# Polarshield_v2_2a.net
KiCad netlist of a schematic drawn in EAGLE
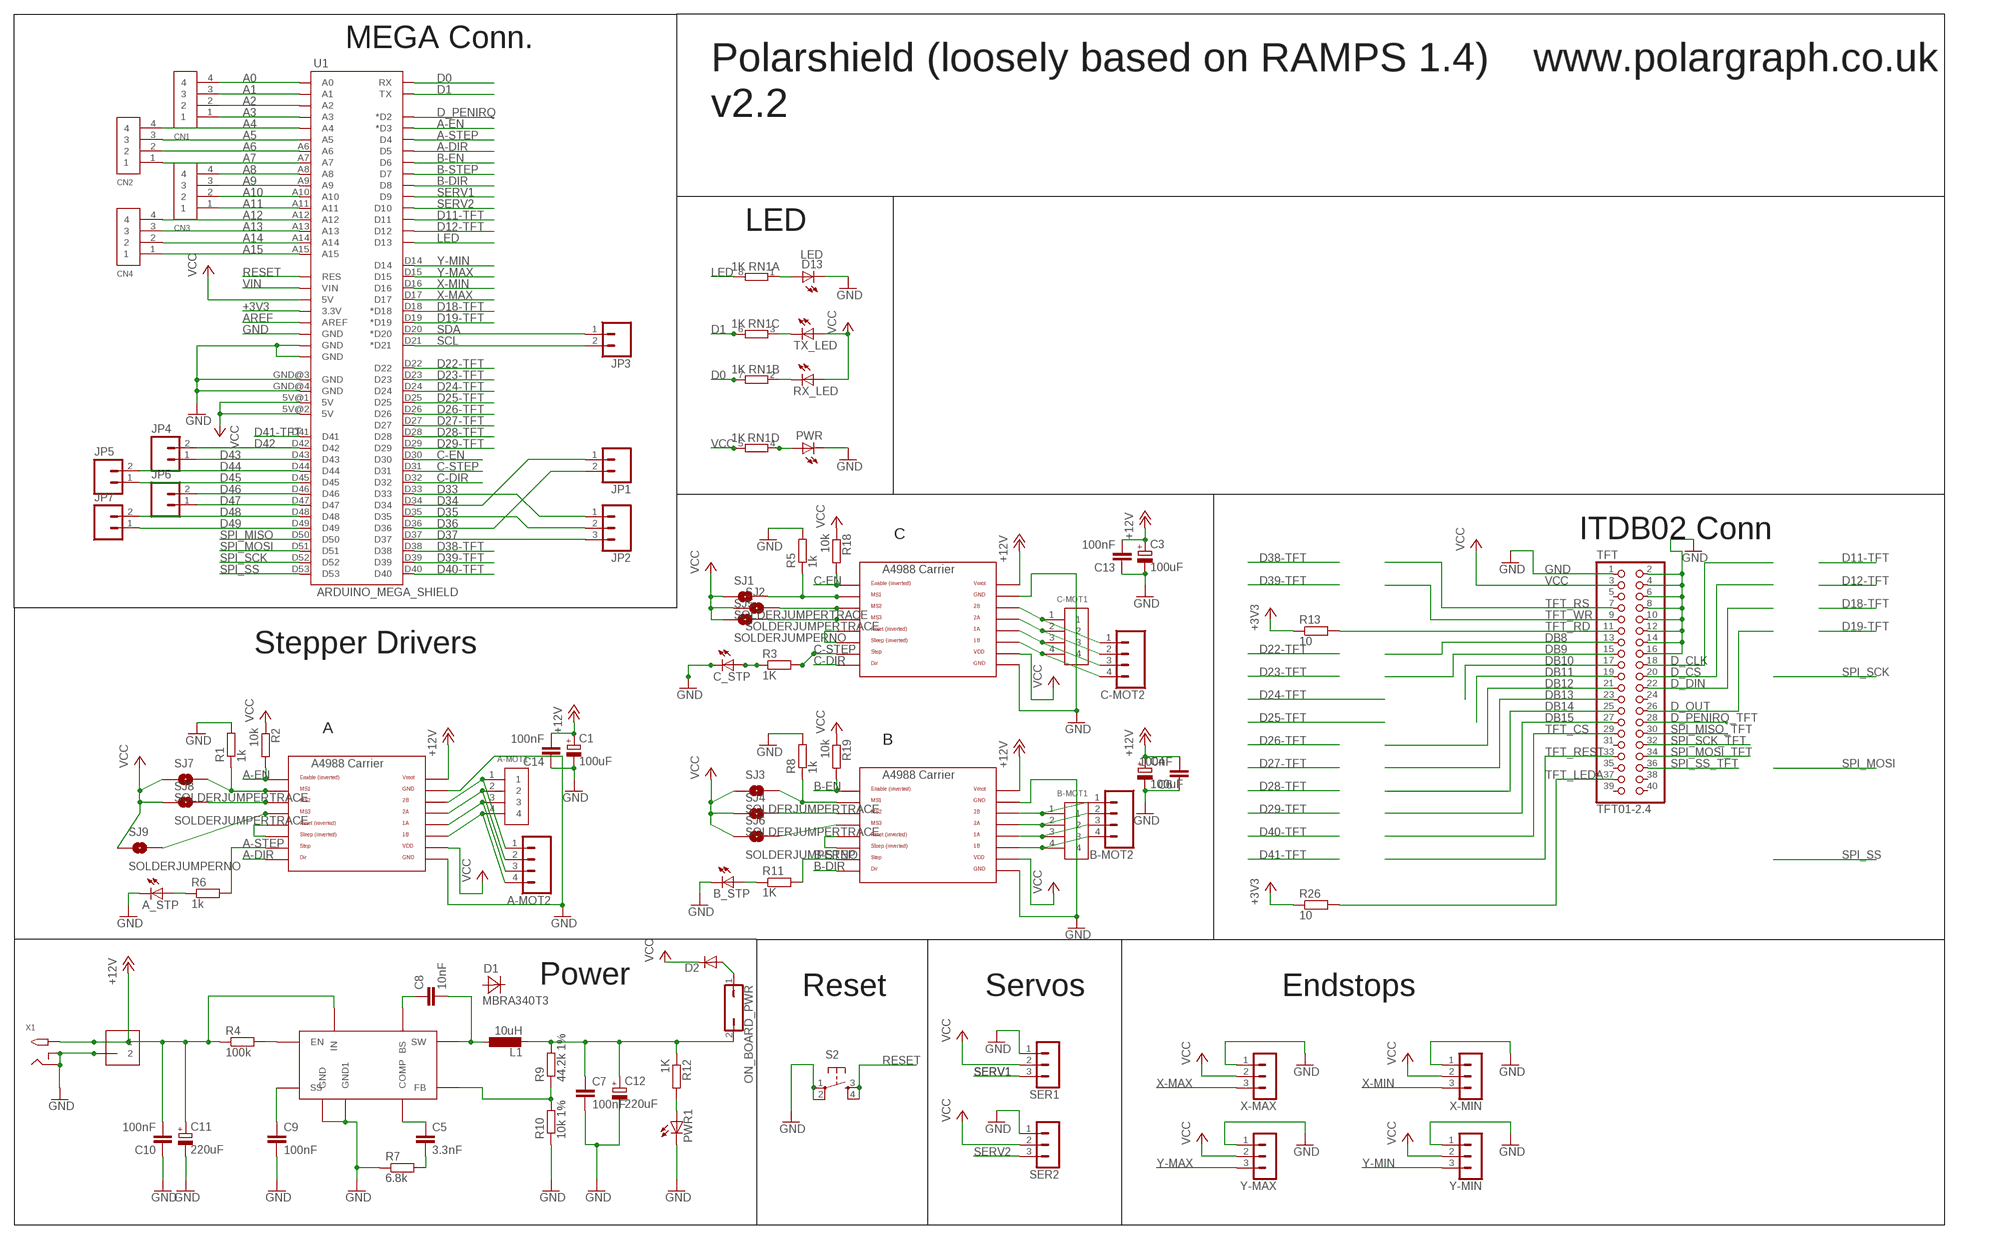
[diagram p0: schematic, sheet 1, part 1 of 2]
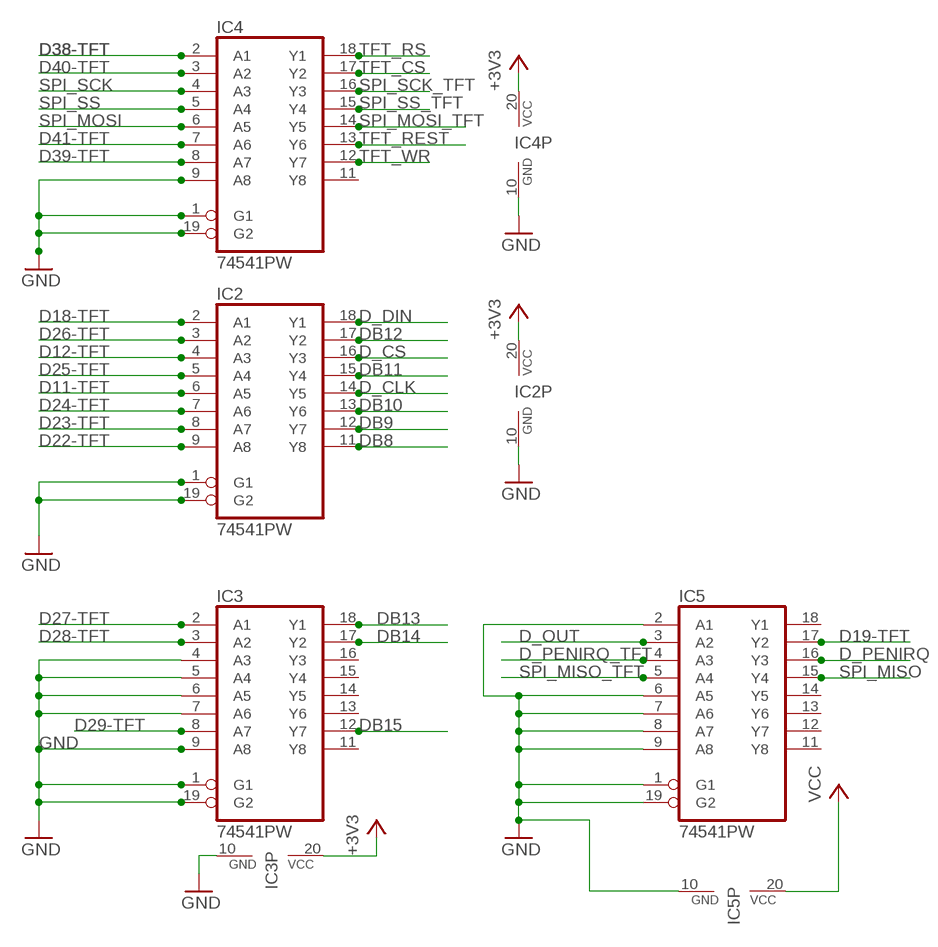
[diagram p1: schematic, sheet 1, part 2 of 2]

(export (version "E")
  (design (tool "Eeschema 10.0.6"))
  (components
    (comp (ref "A-MOT1")
      (value "1X4-BIG")
      (footprint "eagle-import:1X04-BIG")
      (libsource (lib "eagle-import") (part "adafruit_1X4-BIG"))
    )
    (comp (ref "A-MOT2")
      (value "M04SCREW")
      (footprint "eagle-import:SCREWTERMINAL-3.5MM-4")
      (libsource (lib "eagle-import") (part "M04SCREW"))
    )
    (comp (ref "A_STP")
      (value "LEDCHIP-LED0805")
      (footprint "eagle-import:CHIP-LED0805")
      (libsource (lib "eagle-import") (part "LEDCHIP-LED0805"))
    )
    (comp (ref "B-MOT1")
      (value "1X4-BIG")
      (footprint "eagle-import:1X04-BIG")
      (libsource (lib "eagle-import") (part "adafruit_1X4-BIG"))
    )
    (comp (ref "B-MOT2")
      (value "M04SCREW")
      (footprint "eagle-import:SCREWTERMINAL-3.5MM-4")
      (libsource (lib "eagle-import") (part "M04SCREW"))
    )
    (comp (ref "B_STP")
      (value "LEDCHIP-LED0805")
      (footprint "eagle-import:CHIP-LED0805")
      (libsource (lib "eagle-import") (part "LEDCHIP-LED0805"))
    )
    (comp (ref "C-MOT1")
      (value "1X4-BIG")
      (footprint "eagle-import:1X04-BIG")
      (libsource (lib "eagle-import") (part "adafruit_1X4-BIG"))
    )
    (comp (ref "C-MOT2")
      (value "M04SCREW")
      (footprint "eagle-import:SCREWTERMINAL-3.5MM-4")
      (libsource (lib "eagle-import") (part "M04SCREW"))
    )
    (comp (ref "C1")
      (value "100uF")
      (footprint "eagle-import:153CLV-0605")
      (libsource (lib "eagle-import") (part "CPOL-EU153CLV-0605"))
    )
    (comp (ref "C3")
      (value "100uF")
      (footprint "eagle-import:153CLV-0605")
      (libsource (lib "eagle-import") (part "CPOL-EU153CLV-0605"))
    )
    (comp (ref "C4")
      (value "100uF")
      (footprint "eagle-import:153CLV-0605")
      (libsource (lib "eagle-import") (part "CPOL-EU153CLV-0605"))
    )
    (comp (ref "C5")
      (value "3.3nF")
      (footprint "eagle-import:C0805K")
      (libsource (lib "eagle-import") (part "C-EUC0805K"))
    )
    (comp (ref "C6")
      (value "100nF")
      (footprint "eagle-import:C0805")
      (libsource (lib "eagle-import") (part "C-EUC0805"))
    )
    (comp (ref "C7")
      (value "100nF")
      (footprint "eagle-import:C0805K")
      (libsource (lib "eagle-import") (part "C-EUC0805K"))
    )
    (comp (ref "C8")
      (value "10nF")
      (footprint "eagle-import:C0805K")
      (libsource (lib "eagle-import") (part "C-EUC0805K"))
    )
    (comp (ref "C9")
      (value "100nF")
      (footprint "eagle-import:C0805K")
      (libsource (lib "eagle-import") (part "C-EUC0805K"))
    )
    (comp (ref "C10")
      (value "100nF")
      (footprint "eagle-import:C0805K")
      (libsource (lib "eagle-import") (part "C-EUC0805K"))
    )
    (comp (ref "C11")
      (value "220uF")
      (footprint "eagle-import:153CLV-0807")
      (libsource (lib "eagle-import") (part "resistor_CPOL-EU153CLV-0807"))
    )
    (comp (ref "C12")
      (value "220uF")
      (footprint "eagle-import:153CLV-0807")
      (libsource (lib "eagle-import") (part "resistor_CPOL-EU153CLV-0807"))
    )
    (comp (ref "C13")
      (value "100nF")
      (footprint "eagle-import:C0805")
      (libsource (lib "eagle-import") (part "C-EUC0805"))
    )
    (comp (ref "C14")
      (value "100nF")
      (footprint "eagle-import:C0805")
      (libsource (lib "eagle-import") (part "C-EUC0805"))
    )
    (comp (ref "CN1")
      (value "1X4-CLEANBIG")
      (footprint "eagle-import:1X04-CLEANBIG")
      (libsource (lib "eagle-import") (part "1X4-CLEANBIG"))
    )
    (comp (ref "CN2")
      (value "1X4-CLEANBIG")
      (footprint "eagle-import:1X04-CLEANBIG")
      (libsource (lib "eagle-import") (part "1X4-CLEANBIG"))
    )
    (comp (ref "CN3")
      (value "1X4-CLEANBIG")
      (footprint "eagle-import:1X04-CLEANBIG")
      (libsource (lib "eagle-import") (part "1X4-CLEANBIG"))
    )
    (comp (ref "CN4")
      (value "1X4-CLEANBIG")
      (footprint "eagle-import:1X04-CLEANBIG")
      (libsource (lib "eagle-import") (part "1X4-CLEANBIG"))
    )
    (comp (ref "C_STP")
      (value "LEDCHIP-LED0805")
      (footprint "eagle-import:CHIP-LED0805")
      (libsource (lib "eagle-import") (part "LEDCHIP-LED0805"))
    )
    (comp (ref "D1")
      (value "MBRA340T3")
      (footprint "eagle-import:SMA")
      (libsource (lib "eagle-import") (part "MBRA340T3"))
    )
    (comp (ref "D2")
      (value "DIODE-DO214BA")
      (footprint "eagle-import:DO214BA")
      (libsource (lib "eagle-import") (part "DIODE-DO214BA"))
    )
    (comp (ref "D13")
      (value "LED")
      (footprint "eagle-import:CHIP-LED0805")
      (libsource (lib "eagle-import") (part "LEDCHIP-LED0805"))
    )
    (comp (ref "IC1")
      (value "MP2307")
      (footprint "eagle-import:SOIC8")
      (libsource (lib "eagle-import") (part "MP2307"))
    )
    (comp (ref "IC2")
      (value "74541PW")
      (footprint "eagle-import:TSSOP20")
      (libsource (lib "eagle-import") (part "74541PW"))
    )
    (comp (ref "IC3")
      (value "74541PW")
      (footprint "eagle-import:TSSOP20")
      (libsource (lib "eagle-import") (part "74541PW"))
    )
    (comp (ref "IC4")
      (value "74541PW")
      (footprint "eagle-import:TSSOP20")
      (libsource (lib "eagle-import") (part "74541PW"))
    )
    (comp (ref "IC5")
      (value "74541PW")
      (footprint "eagle-import:TSSOP20")
      (libsource (lib "eagle-import") (part "74541PW"))
    )
    (comp (ref "J1")
      (value "1X2-3.5MM")
      (footprint "eagle-import:1X2-3.5MM")
      (libsource (lib "eagle-import") (part "1X2-3.5MM"))
    )
    (comp (ref "JP1")
      (value "M021X02_NO_SILK")
      (footprint "eagle-import:1X02_NO_SILK")
      (libsource (lib "eagle-import") (part "M021X02_NO_SILK"))
    )
    (comp (ref "JP2")
      (value "M031X03_NO_SILK")
      (footprint "eagle-import:1X03_NO_SILK")
      (libsource (lib "eagle-import") (part "M031X03_NO_SILK"))
    )
    (comp (ref "JP3")
      (value "M021X02_NO_SILK")
      (footprint "eagle-import:1X02_NO_SILK")
      (libsource (lib "eagle-import") (part "M021X02_NO_SILK"))
    )
    (comp (ref "JP4")
      (value "M021X02_NO_SILK")
      (footprint "eagle-import:1X02_NO_SILK")
      (libsource (lib "eagle-import") (part "M021X02_NO_SILK"))
    )
    (comp (ref "JP5")
      (value "M021X02_NO_SILK")
      (footprint "eagle-import:1X02_NO_SILK")
      (libsource (lib "eagle-import") (part "M021X02_NO_SILK"))
    )
    (comp (ref "JP6")
      (value "M021X02_NO_SILK")
      (footprint "eagle-import:1X02_NO_SILK")
      (libsource (lib "eagle-import") (part "M021X02_NO_SILK"))
    )
    (comp (ref "JP7")
      (value "M021X02_NO_SILK")
      (footprint "eagle-import:1X02_NO_SILK")
      (libsource (lib "eagle-import") (part "M021X02_NO_SILK"))
    )
    (comp (ref "L1")
      (value "10uH")
      (footprint "eagle-import:PIS2816")
      (libsource (lib "eagle-import") (part "L-EUPIS2816"))
    )
    (comp (ref "ON_BOARD_PWR")
      (value "JP1Q")
      (footprint "eagle-import:JP1")
      (libsource (lib "eagle-import") (part "JP1Q"))
    )
    (comp (ref "PWR")
      (value "LEDCHIP-LED0805")
      (footprint "eagle-import:CHIP-LED0805")
      (libsource (lib "eagle-import") (part "LEDCHIP-LED0805"))
    )
    (comp (ref "PWR1")
      (value "LEDCHIP-LED0805")
      (footprint "eagle-import:CHIP-LED0805")
      (libsource (lib "eagle-import") (part "LEDCHIP-LED0805"))
    )
    (comp (ref "R1")
      (value "1k")
      (footprint "eagle-import:R0805")
      (libsource (lib "eagle-import") (part "R-EU_R0805"))
    )
    (comp (ref "R2")
      (value "10k")
      (footprint "eagle-import:R0805")
      (libsource (lib "eagle-import") (part "R-EU_R0805"))
    )
    (comp (ref "R3")
      (value "1K")
      (footprint "eagle-import:R0805")
      (libsource (lib "eagle-import") (part "R-EU_R0805"))
    )
    (comp (ref "R4")
      (value "100k")
      (footprint "eagle-import:R0805")
      (libsource (lib "eagle-import") (part "resistor_R-EU_R0805"))
    )
    (comp (ref "R5")
      (value "1k")
      (footprint "eagle-import:R0805")
      (libsource (lib "eagle-import") (part "R-EU_R0805"))
    )
    (comp (ref "R6")
      (value "1k")
      (footprint "eagle-import:R0805")
      (libsource (lib "eagle-import") (part "R-EU_R0805"))
    )
    (comp (ref "R7")
      (value "6.8k")
      (footprint "eagle-import:R0805")
      (libsource (lib "eagle-import") (part "resistor_R-EU_R0805"))
    )
    (comp (ref "R8")
      (value "1k")
      (footprint "eagle-import:R0805")
      (libsource (lib "eagle-import") (part "R-EU_R0805"))
    )
    (comp (ref "R9")
      (value "44.2k 1%")
      (footprint "eagle-import:R0805")
      (libsource (lib "eagle-import") (part "resistor_R-EU_R0805"))
    )
    (comp (ref "R10")
      (value "10k 1%")
      (footprint "eagle-import:R0805")
      (libsource (lib "eagle-import") (part "resistor_R-EU_R0805"))
    )
    (comp (ref "R11")
      (value "1K")
      (footprint "eagle-import:R0805")
      (libsource (lib "eagle-import") (part "R-EU_R0805"))
    )
    (comp (ref "R12")
      (value "1K")
      (footprint "eagle-import:R0805")
      (libsource (lib "eagle-import") (part "R-EU_R0805"))
    )
    (comp (ref "R13")
      (value "10")
      (footprint "eagle-import:R0805")
      (libsource (lib "eagle-import") (part "resistor_R-EU_R0805"))
    )
    (comp (ref "R18")
      (value "10k")
      (footprint "eagle-import:R0805")
      (libsource (lib "eagle-import") (part "R-EU_R0805"))
    )
    (comp (ref "R19")
      (value "10k")
      (footprint "eagle-import:R0805")
      (libsource (lib "eagle-import") (part "R-EU_R0805"))
    )
    (comp (ref "R26")
      (value "10")
      (footprint "eagle-import:R0805")
      (libsource (lib "eagle-import") (part "resistor_R-EU_R0805"))
    )
    (comp (ref "RN1")
      (value "1K")
      (footprint "eagle-import:EXBS8V")
      (libsource (lib "eagle-import") (part "4R-NEXBS8V"))
    )
    (comp (ref "RX_LED")
      (value "LEDCHIP-LED0805")
      (footprint "eagle-import:CHIP-LED0805")
      (libsource (lib "eagle-import") (part "LEDCHIP-LED0805"))
    )
    (comp (ref "S2")
      (value "TAC_SWITCHPTH")
      (footprint "eagle-import:TACTILE-PTH")
      (libsource (lib "eagle-import") (part "TAC_SWITCHPTH"))
    )
    (comp (ref "SER1")
      (value "3PIN-HEADER")
      (footprint "eagle-import:3PIN-HEADER")
      (libsource (lib "eagle-import") (part "3PIN-HEADER"))
    )
    (comp (ref "SER2")
      (value "3PIN-HEADER")
      (footprint "eagle-import:3PIN-HEADER")
      (libsource (lib "eagle-import") (part "3PIN-HEADER"))
    )
    (comp (ref "SJ1")
      (value "SOLDERJUMPERTRACE")
      (footprint "eagle-import:SJ_2S-TRACE")
      (libsource (lib "eagle-import") (part "SOLDERJUMPERTRACE"))
    )
    (comp (ref "SJ2")
      (value "SOLDERJUMPERTRACE")
      (footprint "eagle-import:SJ_2S-TRACE")
      (libsource (lib "eagle-import") (part "SOLDERJUMPERTRACE"))
    )
    (comp (ref "SJ3")
      (value "SOLDERJUMPERTRACE")
      (footprint "eagle-import:SJ_2S-TRACE")
      (libsource (lib "eagle-import") (part "SOLDERJUMPERTRACE"))
    )
    (comp (ref "SJ4")
      (value "SOLDERJUMPERTRACE")
      (footprint "eagle-import:SJ_2S-TRACE")
      (libsource (lib "eagle-import") (part "SOLDERJUMPERTRACE"))
    )
    (comp (ref "SJ5")
      (value "SOLDERJUMPERNO")
      (footprint "eagle-import:SJ_2S-NO")
      (libsource (lib "eagle-import") (part "SOLDERJUMPERNO"))
    )
    (comp (ref "SJ6")
      (value "SOLDERJUMPERNO")
      (footprint "eagle-import:SJ_2S-NO")
      (libsource (lib "eagle-import") (part "SOLDERJUMPERNO"))
    )
    (comp (ref "SJ7")
      (value "SOLDERJUMPERTRACE")
      (footprint "eagle-import:SJ_2S-TRACE")
      (libsource (lib "eagle-import") (part "SOLDERJUMPERTRACE"))
    )
    (comp (ref "SJ8")
      (value "SOLDERJUMPERTRACE")
      (footprint "eagle-import:SJ_2S-TRACE")
      (libsource (lib "eagle-import") (part "SOLDERJUMPERTRACE"))
    )
    (comp (ref "SJ9")
      (value "SOLDERJUMPERNO")
      (footprint "eagle-import:SJ_2S-NO")
      (libsource (lib "eagle-import") (part "SOLDERJUMPERNO"))
    )
    (comp (ref "TFT")
      (value "TFT01-2.4")
      (footprint "eagle-import:TFT01-2.4")
      (libsource (lib "eagle-import") (part "TFT01-2.4"))
    )
    (comp (ref "TX_LED")
      (value "LEDCHIP-LED0805")
      (footprint "eagle-import:CHIP-LED0805")
      (libsource (lib "eagle-import") (part "LEDCHIP-LED0805"))
    )
    (comp (ref "U$1")
      (value "A4988BREAKOUT")
      (footprint "eagle-import:A4988BREAKOUT")
      (libsource (lib "eagle-import") (part "A4988BREAKOUT"))
    )
    (comp (ref "U$6")
      (value "A4988BREAKOUT")
      (footprint "eagle-import:A4988BREAKOUT")
      (libsource (lib "eagle-import") (part "A4988BREAKOUT"))
    )
    (comp (ref "U$7")
      (value "A4988BREAKOUT")
      (footprint "eagle-import:A4988BREAKOUT")
      (libsource (lib "eagle-import") (part "A4988BREAKOUT"))
    )
    (comp (ref "U1")
      (value "ARDUINO_MEGA_SHIELD")
      (footprint "eagle-import:ARDUINO_MEGA_SHIELD")
      (libsource (lib "eagle-import") (part "ARDUINO_MEGA_SHIELD"))
    )
    (comp (ref "X-MAX")
      (value "3PIN-HEADER")
      (footprint "eagle-import:3PIN-HEADER")
      (libsource (lib "eagle-import") (part "3PIN-HEADER"))
    )
    (comp (ref "X-MIN")
      (value "3PIN-HEADER")
      (footprint "eagle-import:3PIN-HEADER")
      (libsource (lib "eagle-import") (part "3PIN-HEADER"))
    )
    (comp (ref "X1")
      (value "2.1MMJACKTHM")
      (footprint "eagle-import:PJ-102A")
      (libsource (lib "eagle-import") (part "2.1MMJACKTHM"))
    )
    (comp (ref "Y-MAX")
      (value "3PIN-HEADER")
      (footprint "eagle-import:3PIN-HEADER")
      (libsource (lib "eagle-import") (part "3PIN-HEADER"))
    )
    (comp (ref "Y-MIN")
      (value "3PIN-HEADER")
      (footprint "eagle-import:3PIN-HEADER")
      (libsource (lib "eagle-import") (part "3PIN-HEADER"))
    )
  )
  (nets
    (net (code "1") (name "+3V3") (class "Default")
      (node (ref "IC2") (pin "20") (pinfunction "VCC_20") (pintype "power_in"))
      (node (ref "IC3") (pin "20") (pinfunction "VCC_20") (pintype "power_in"))
      (node (ref "IC4") (pin "20") (pinfunction "VCC_20") (pintype "power_in"))
      (node (ref "R13") (pin "1") (pinfunction "1_1") (pintype "passive"))
      (node (ref "R26") (pin "1") (pinfunction "1_1") (pintype "passive"))
      (node (ref "U1") (pin "3.3V") (pinfunction "3.3V_3.3V") (pintype "bidirectional"))
    )
    (net (code "2") (name "+12V") (class "Default")
      (node (ref "C1") (pin "+") (pinfunction "+_+") (pintype "passive"))
      (node (ref "C10") (pin "2") (pinfunction "2_2") (pintype "passive"))
      (node (ref "C11") (pin "+") (pinfunction "+_+") (pintype "passive"))
      (node (ref "C13") (pin "2") (pinfunction "2_2") (pintype "passive"))
      (node (ref "C14") (pin "2") (pinfunction "2_2") (pintype "passive"))
      (node (ref "C3") (pin "+") (pinfunction "+_+") (pintype "passive"))
      (node (ref "C4") (pin "+") (pinfunction "+_+") (pintype "passive"))
      (node (ref "C6") (pin "2") (pinfunction "2_2") (pintype "passive"))
      (node (ref "IC1") (pin "IN") (pinfunction "IN_IN") (pintype "bidirectional"))
      (node (ref "J1") (pin "1") (pinfunction "1_1") (pintype "passive"))
      (node (ref "R4") (pin "1") (pinfunction "1_1") (pintype "passive"))
      (node (ref "U$1") (pin "VMOT") (pinfunction "VMOT_VMOT") (pintype "power_in"))
      (node (ref "U$6") (pin "VMOT") (pinfunction "VMOT_VMOT") (pintype "power_in"))
      (node (ref "U$7") (pin "VMOT") (pinfunction "VMOT_VMOT") (pintype "power_in"))
      (node (ref "X1") (pin "TIP") (pinfunction "TIP_TIP") (pintype "bidirectional"))
    )
    (net (code "3") (name "/A-DIR") (class "Default")
      (node (ref "U$1") (pin "DIR") (pinfunction "DIR_DIR") (pintype "input"))
      (node (ref "U1") (pin "D5") (pinfunction "D5_D5") (pintype "bidirectional"))
    )
    (net (code "4") (name "/A-EN") (class "Default")
      (node (ref "R2") (pin "2") (pinfunction "2_2") (pintype "passive"))
      (node (ref "U$1") (pin "EN") (pinfunction "EN_EN") (pintype "input"))
      (node (ref "U1") (pin "D3") (pinfunction "*D3_D3") (pintype "bidirectional"))
    )
    (net (code "5") (name "/A-STEP") (class "Default")
      (node (ref "R6") (pin "2") (pinfunction "2_2") (pintype "passive"))
      (node (ref "U$1") (pin "STEP") (pinfunction "STEP_STEP") (pintype "input"))
      (node (ref "U1") (pin "D4") (pinfunction "D4_D4") (pintype "bidirectional"))
    )
    (net (code "6") (name "/A0") (class "Default")
      (node (ref "CN1") (pin "4") (pinfunction "4_4") (pintype "bidirectional"))
      (node (ref "U1") (pin "A0") (pinfunction "A0_A0") (pintype "bidirectional"))
    )
    (net (code "7") (name "/A1") (class "Default")
      (node (ref "CN1") (pin "3") (pinfunction "3_3") (pintype "bidirectional"))
      (node (ref "U1") (pin "A1") (pinfunction "A1_A1") (pintype "bidirectional"))
    )
    (net (code "8") (name "/A2") (class "Default")
      (node (ref "CN1") (pin "2") (pinfunction "2_2") (pintype "bidirectional"))
      (node (ref "U1") (pin "A2") (pinfunction "A2_A2") (pintype "bidirectional"))
    )
    (net (code "9") (name "/A3") (class "Default")
      (node (ref "CN1") (pin "1") (pinfunction "1_1") (pintype "bidirectional"))
      (node (ref "U1") (pin "A3") (pinfunction "A3_A3") (pintype "bidirectional"))
    )
    (net (code "10") (name "/A4") (class "Default")
      (node (ref "CN2") (pin "4") (pinfunction "4_4") (pintype "bidirectional"))
      (node (ref "U1") (pin "A4") (pinfunction "A4_A4") (pintype "bidirectional"))
    )
    (net (code "11") (name "/A5") (class "Default")
      (node (ref "CN2") (pin "3") (pinfunction "3_3") (pintype "bidirectional"))
      (node (ref "U1") (pin "A5") (pinfunction "A5_A5") (pintype "bidirectional"))
    )
    (net (code "12") (name "/A6") (class "Default")
      (node (ref "CN2") (pin "2") (pinfunction "2_2") (pintype "bidirectional"))
      (node (ref "U1") (pin "A6") (pinfunction "A6_A6") (pintype "bidirectional"))
    )
    (net (code "13") (name "/A7") (class "Default")
      (node (ref "CN2") (pin "1") (pinfunction "1_1") (pintype "bidirectional"))
      (node (ref "U1") (pin "A7") (pinfunction "A7_A7") (pintype "bidirectional"))
    )
    (net (code "14") (name "/A8") (class "Default")
      (node (ref "CN3") (pin "4") (pinfunction "4_4") (pintype "bidirectional"))
      (node (ref "U1") (pin "A8") (pinfunction "A8_A8") (pintype "bidirectional"))
    )
    (net (code "15") (name "/A9") (class "Default")
      (node (ref "CN3") (pin "3") (pinfunction "3_3") (pintype "bidirectional"))
      (node (ref "U1") (pin "A9") (pinfunction "A9_A9") (pintype "bidirectional"))
    )
    (net (code "16") (name "/A10") (class "Default")
      (node (ref "CN3") (pin "2") (pinfunction "2_2") (pintype "bidirectional"))
      (node (ref "U1") (pin "A10") (pinfunction "A10_A10") (pintype "bidirectional"))
    )
    (net (code "17") (name "/A11") (class "Default")
      (node (ref "CN3") (pin "1") (pinfunction "1_1") (pintype "bidirectional"))
      (node (ref "U1") (pin "A11") (pinfunction "A11_A11") (pintype "bidirectional"))
    )
    (net (code "18") (name "/A12") (class "Default")
      (node (ref "CN4") (pin "4") (pinfunction "4_4") (pintype "bidirectional"))
      (node (ref "U1") (pin "A12") (pinfunction "A12_A12") (pintype "bidirectional"))
    )
    (net (code "19") (name "/A13") (class "Default")
      (node (ref "CN4") (pin "3") (pinfunction "3_3") (pintype "bidirectional"))
      (node (ref "U1") (pin "A13") (pinfunction "A13_A13") (pintype "bidirectional"))
    )
    (net (code "20") (name "/A14") (class "Default")
      (node (ref "CN4") (pin "2") (pinfunction "2_2") (pintype "bidirectional"))
      (node (ref "U1") (pin "A14") (pinfunction "A14_A14") (pintype "bidirectional"))
    )
    (net (code "21") (name "/A15") (class "Default")
      (node (ref "CN4") (pin "1") (pinfunction "1_1") (pintype "bidirectional"))
      (node (ref "U1") (pin "A15") (pinfunction "A15_A15") (pintype "bidirectional"))
    )
    (net (code "22") (name "/AREF") (class "Default")
      (node (ref "U1") (pin "AREF") (pinfunction "AREF_AREF") (pintype "bidirectional"))
    )
    (net (code "23") (name "/B-DIR") (class "Default")
      (node (ref "U$7") (pin "DIR") (pinfunction "DIR_DIR") (pintype "input"))
      (node (ref "U1") (pin "D8") (pinfunction "D8_D8") (pintype "bidirectional"))
    )
    (net (code "24") (name "/B-EN") (class "Default")
      (node (ref "R19") (pin "2") (pinfunction "2_2") (pintype "passive"))
      (node (ref "U$7") (pin "EN") (pinfunction "EN_EN") (pintype "input"))
      (node (ref "U1") (pin "D6") (pinfunction "D6_D6") (pintype "bidirectional"))
    )
    (net (code "25") (name "/B-STEP") (class "Default")
      (node (ref "R11") (pin "2") (pinfunction "2_2") (pintype "passive"))
      (node (ref "U$7") (pin "STEP") (pinfunction "STEP_STEP") (pintype "input"))
      (node (ref "U1") (pin "D7") (pinfunction "D7_D7") (pintype "bidirectional"))
    )
    (net (code "26") (name "/C-DIR") (class "Default")
      (node (ref "U$6") (pin "DIR") (pinfunction "DIR_DIR") (pintype "input"))
      (node (ref "U1") (pin "D32") (pinfunction "D32_D32") (pintype "bidirectional"))
    )
    (net (code "27") (name "/C-EN") (class "Default")
      (node (ref "R18") (pin "2") (pinfunction "2_2") (pintype "passive"))
      (node (ref "U$6") (pin "EN") (pinfunction "EN_EN") (pintype "input"))
      (node (ref "U1") (pin "D30") (pinfunction "D30_D30") (pintype "bidirectional"))
    )
    (net (code "28") (name "/C-STEP") (class "Default")
      (node (ref "R3") (pin "2") (pinfunction "2_2") (pintype "passive"))
      (node (ref "U$6") (pin "STEP") (pinfunction "STEP_STEP") (pintype "input"))
      (node (ref "U1") (pin "D31") (pinfunction "D31_D31") (pintype "bidirectional"))
    )
    (net (code "29") (name "/D0") (class "Default")
      (node (ref "RN1") (pin "7") (pinfunction "2_7") (pintype "passive"))
      (node (ref "U1") (pin "RX") (pinfunction "RX_RX") (pintype "bidirectional"))
    )
    (net (code "30") (name "/D1") (class "Default")
      (node (ref "RN1") (pin "6") (pinfunction "2_6") (pintype "passive"))
      (node (ref "U1") (pin "TX") (pinfunction "TX_TX") (pintype "bidirectional"))
    )
    (net (code "31") (name "/D11-TFT") (class "Default")
      (node (ref "IC2") (pin "6") (pinfunction "A5_6") (pintype "input"))
      (node (ref "U1") (pin "D11") (pinfunction "D11_D11") (pintype "bidirectional"))
    )
    (net (code "32") (name "/D12-TFT") (class "Default")
      (node (ref "IC2") (pin "4") (pinfunction "A3_4") (pintype "input"))
      (node (ref "U1") (pin "D12") (pinfunction "D12_D12") (pintype "bidirectional"))
    )
    (net (code "33") (name "/D18-TFT") (class "Default")
      (node (ref "IC2") (pin "2") (pinfunction "A1_2") (pintype "input"))
      (node (ref "U1") (pin "D18") (pinfunction "*D18_D18") (pintype "bidirectional"))
    )
    (net (code "34") (name "/D19-TFT") (class "Default")
      (node (ref "IC5") (pin "17") (pinfunction "Y2_17") (pintype "tri_state"))
      (node (ref "U1") (pin "D19") (pinfunction "*D19_D19") (pintype "bidirectional"))
    )
    (net (code "35") (name "/D22-TFT") (class "Default")
      (node (ref "IC2") (pin "9") (pinfunction "A8_9") (pintype "input"))
      (node (ref "U1") (pin "D22") (pinfunction "D22_D22") (pintype "bidirectional"))
    )
    (net (code "36") (name "/D23-TFT") (class "Default")
      (node (ref "IC2") (pin "8") (pinfunction "A7_8") (pintype "input"))
      (node (ref "U1") (pin "D23") (pinfunction "D23_D23") (pintype "bidirectional"))
    )
    (net (code "37") (name "/D24-TFT") (class "Default")
      (node (ref "IC2") (pin "7") (pinfunction "A6_7") (pintype "input"))
      (node (ref "U1") (pin "D24") (pinfunction "D24_D24") (pintype "bidirectional"))
    )
    (net (code "38") (name "/D25-TFT") (class "Default")
      (node (ref "IC2") (pin "5") (pinfunction "A4_5") (pintype "input"))
      (node (ref "U1") (pin "D25") (pinfunction "D25_D25") (pintype "bidirectional"))
    )
    (net (code "39") (name "/D26-TFT") (class "Default")
      (node (ref "IC2") (pin "3") (pinfunction "A2_3") (pintype "input"))
      (node (ref "U1") (pin "D26") (pinfunction "D26_D26") (pintype "bidirectional"))
    )
    (net (code "40") (name "/D27-TFT") (class "Default")
      (node (ref "IC3") (pin "2") (pinfunction "A1_2") (pintype "input"))
      (node (ref "U1") (pin "D27") (pinfunction "D27_D27") (pintype "bidirectional"))
    )
    (net (code "41") (name "/D28-TFT") (class "Default")
      (node (ref "IC3") (pin "3") (pinfunction "A2_3") (pintype "input"))
      (node (ref "U1") (pin "D28") (pinfunction "D28_D28") (pintype "bidirectional"))
    )
    (net (code "42") (name "/D29-TFT") (class "Default")
      (node (ref "IC3") (pin "8") (pinfunction "A7_8") (pintype "input"))
      (node (ref "U1") (pin "D29") (pinfunction "D29_D29") (pintype "bidirectional"))
    )
    (net (code "43") (name "/D33") (class "Default")
      (node (ref "JP2") (pin "1") (pinfunction "1_1") (pintype "passive"))
      (node (ref "U1") (pin "D33") (pinfunction "D33_D33") (pintype "bidirectional"))
    )
    (net (code "44") (name "/D34") (class "Default")
      (node (ref "JP1") (pin "1") (pinfunction "1_1") (pintype "passive"))
      (node (ref "U1") (pin "D34") (pinfunction "D34_D34") (pintype "bidirectional"))
    )
    (net (code "45") (name "/D35") (class "Default")
      (node (ref "JP2") (pin "2") (pinfunction "2_2") (pintype "passive"))
      (node (ref "U1") (pin "D35") (pinfunction "D35_D35") (pintype "bidirectional"))
    )
    (net (code "46") (name "/D36") (class "Default")
      (node (ref "JP1") (pin "2") (pinfunction "2_2") (pintype "passive"))
      (node (ref "U1") (pin "D36") (pinfunction "D36_D36") (pintype "bidirectional"))
    )
    (net (code "47") (name "/D37") (class "Default")
      (node (ref "JP2") (pin "3") (pinfunction "3_3") (pintype "passive"))
      (node (ref "U1") (pin "D37") (pinfunction "D37_D37") (pintype "bidirectional"))
    )
    (net (code "48") (name "/D38-TFT") (class "Default")
      (node (ref "IC4") (pin "2") (pinfunction "A1_2") (pintype "input"))
      (node (ref "U1") (pin "D38") (pinfunction "D38_D38") (pintype "bidirectional"))
    )
    (net (code "49") (name "/D39-TFT") (class "Default")
      (node (ref "IC4") (pin "8") (pinfunction "A7_8") (pintype "input"))
      (node (ref "U1") (pin "D39") (pinfunction "D39_D39") (pintype "bidirectional"))
    )
    (net (code "50") (name "/D40-TFT") (class "Default")
      (node (ref "IC4") (pin "3") (pinfunction "A2_3") (pintype "input"))
      (node (ref "U1") (pin "D40") (pinfunction "D40_D40") (pintype "bidirectional"))
    )
    (net (code "51") (name "/D41-TFT") (class "Default")
      (node (ref "IC4") (pin "7") (pinfunction "A6_7") (pintype "input"))
      (node (ref "U1") (pin "D41") (pinfunction "D41_D41") (pintype "bidirectional"))
    )
    (net (code "52") (name "/D42") (class "Default")
      (node (ref "JP4") (pin "2") (pinfunction "2_2") (pintype "passive"))
      (node (ref "U1") (pin "D42") (pinfunction "D42_D42") (pintype "bidirectional"))
    )
    (net (code "53") (name "/D43") (class "Default")
      (node (ref "JP4") (pin "1") (pinfunction "1_1") (pintype "passive"))
      (node (ref "U1") (pin "D43") (pinfunction "D43_D43") (pintype "bidirectional"))
    )
    (net (code "54") (name "/D44") (class "Default")
      (node (ref "JP5") (pin "2") (pinfunction "2_2") (pintype "passive"))
      (node (ref "U1") (pin "D44") (pinfunction "D44_D44") (pintype "bidirectional"))
    )
    (net (code "55") (name "/D45") (class "Default")
      (node (ref "JP5") (pin "1") (pinfunction "1_1") (pintype "passive"))
      (node (ref "U1") (pin "D45") (pinfunction "D45_D45") (pintype "bidirectional"))
    )
    (net (code "56") (name "/D46") (class "Default")
      (node (ref "JP6") (pin "2") (pinfunction "2_2") (pintype "passive"))
      (node (ref "U1") (pin "D46") (pinfunction "D46_D46") (pintype "bidirectional"))
    )
    (net (code "57") (name "/D47") (class "Default")
      (node (ref "JP6") (pin "1") (pinfunction "1_1") (pintype "passive"))
      (node (ref "U1") (pin "D47") (pinfunction "D47_D47") (pintype "bidirectional"))
    )
    (net (code "58") (name "/D48") (class "Default")
      (node (ref "JP7") (pin "2") (pinfunction "2_2") (pintype "passive"))
      (node (ref "U1") (pin "D48") (pinfunction "D48_D48") (pintype "bidirectional"))
    )
    (net (code "59") (name "/D49") (class "Default")
      (node (ref "JP7") (pin "1") (pinfunction "1_1") (pintype "passive"))
      (node (ref "U1") (pin "D49") (pinfunction "D49_D49") (pintype "bidirectional"))
    )
    (net (code "60") (name "/DB8") (class "Default")
      (node (ref "IC2") (pin "11") (pinfunction "Y8_11") (pintype "tri_state"))
      (node (ref "TFT") (pin "13") (pinfunction "13_13") (pintype "passive"))
    )
    (net (code "61") (name "/DB9") (class "Default")
      (node (ref "IC2") (pin "12") (pinfunction "Y7_12") (pintype "tri_state"))
      (node (ref "TFT") (pin "15") (pinfunction "15_15") (pintype "passive"))
    )
    (net (code "62") (name "/DB10") (class "Default")
      (node (ref "IC2") (pin "13") (pinfunction "Y6_13") (pintype "tri_state"))
      (node (ref "TFT") (pin "17") (pinfunction "17_17") (pintype "passive"))
    )
    (net (code "63") (name "/DB11") (class "Default")
      (node (ref "IC2") (pin "15") (pinfunction "Y4_15") (pintype "tri_state"))
      (node (ref "TFT") (pin "19") (pinfunction "19_19") (pintype "passive"))
    )
    (net (code "64") (name "/DB12") (class "Default")
      (node (ref "IC2") (pin "17") (pinfunction "Y2_17") (pintype "tri_state"))
      (node (ref "TFT") (pin "21") (pinfunction "21_21") (pintype "passive"))
    )
    (net (code "65") (name "/DB13") (class "Default")
      (node (ref "IC3") (pin "18") (pinfunction "Y1_18") (pintype "tri_state"))
      (node (ref "TFT") (pin "23") (pinfunction "23_23") (pintype "passive"))
    )
    (net (code "66") (name "/DB14") (class "Default")
      (node (ref "IC3") (pin "17") (pinfunction "Y2_17") (pintype "tri_state"))
      (node (ref "TFT") (pin "25") (pinfunction "25_25") (pintype "passive"))
    )
    (net (code "67") (name "/DB15") (class "Default")
      (node (ref "IC3") (pin "12") (pinfunction "Y7_12") (pintype "tri_state"))
      (node (ref "TFT") (pin "27") (pinfunction "27_27") (pintype "passive"))
    )
    (net (code "68") (name "/D_CLK") (class "Default")
      (node (ref "IC2") (pin "14") (pinfunction "Y5_14") (pintype "tri_state"))
      (node (ref "TFT") (pin "18") (pinfunction "18_18") (pintype "passive"))
    )
    (net (code "69") (name "/D_CS") (class "Default")
      (node (ref "IC2") (pin "16") (pinfunction "Y3_16") (pintype "tri_state"))
      (node (ref "TFT") (pin "20") (pinfunction "20_20") (pintype "passive"))
    )
    (net (code "70") (name "/D_DIN") (class "Default")
      (node (ref "IC2") (pin "18") (pinfunction "Y1_18") (pintype "tri_state"))
      (node (ref "TFT") (pin "22") (pinfunction "22_22") (pintype "passive"))
    )
    (net (code "71") (name "/D_OUT") (class "Default")
      (node (ref "IC5") (pin "3") (pinfunction "A2_3") (pintype "input"))
      (node (ref "TFT") (pin "26") (pinfunction "26_26") (pintype "passive"))
    )
    (net (code "72") (name "/D_PENIRQ") (class "Default")
      (node (ref "IC5") (pin "16") (pinfunction "Y3_16") (pintype "tri_state"))
      (node (ref "U1") (pin "D2") (pinfunction "*D2_D2") (pintype "bidirectional"))
    )
    (net (code "73") (name "/D_PENIRQ_TFT") (class "Default")
      (node (ref "IC5") (pin "4") (pinfunction "A3_4") (pintype "input"))
      (node (ref "TFT") (pin "28") (pinfunction "28_28") (pintype "passive"))
    )
    (net (code "74") (name "/LED") (class "Default")
      (node (ref "RN1") (pin "8") (pinfunction "2_8") (pintype "passive"))
      (node (ref "U1") (pin "D13") (pinfunction "D13_D13") (pintype "bidirectional"))
    )
    (net (code "75") (name "/RESET") (class "Default")
      (node (ref "S2") (pin "3") (pinfunction "3_3") (pintype "passive"))
      (node (ref "S2") (pin "4") (pinfunction "4_4") (pintype "passive"))
      (node (ref "U1") (pin "RES") (pinfunction "RES_RES") (pintype "bidirectional"))
    )
    (net (code "76") (name "/SCL") (class "Default")
      (node (ref "JP3") (pin "2") (pinfunction "2_2") (pintype "passive"))
      (node (ref "U1") (pin "D21") (pinfunction "*D21_D21") (pintype "bidirectional"))
    )
    (net (code "77") (name "/SDA") (class "Default")
      (node (ref "JP3") (pin "1") (pinfunction "1_1") (pintype "passive"))
      (node (ref "U1") (pin "D20") (pinfunction "*D20_D20") (pintype "bidirectional"))
    )
    (net (code "78") (name "/SERV1") (class "Default")
      (node (ref "SER1") (pin "3") (pinfunction "3_3") (pintype "passive"))
      (node (ref "U1") (pin "D9") (pinfunction "D9_D9") (pintype "bidirectional"))
    )
    (net (code "79") (name "/SERV2") (class "Default")
      (node (ref "SER2") (pin "3") (pinfunction "3_3") (pintype "passive"))
      (node (ref "U1") (pin "D10") (pinfunction "D10_D10") (pintype "bidirectional"))
    )
    (net (code "80") (name "/SPI_MISO") (class "Default")
      (node (ref "IC5") (pin "15") (pinfunction "Y4_15") (pintype "tri_state"))
      (node (ref "U1") (pin "D50") (pinfunction "D50_D50") (pintype "bidirectional"))
    )
    (net (code "81") (name "/SPI_MISO_TFT") (class "Default")
      (node (ref "IC5") (pin "5") (pinfunction "A4_5") (pintype "input"))
      (node (ref "TFT") (pin "30") (pinfunction "30_30") (pintype "passive"))
    )
    (net (code "82") (name "/SPI_MOSI") (class "Default")
      (node (ref "IC4") (pin "6") (pinfunction "A5_6") (pintype "input"))
      (node (ref "U1") (pin "D51") (pinfunction "D51_D51") (pintype "bidirectional"))
    )
    (net (code "83") (name "/SPI_MOSI_TFT") (class "Default")
      (node (ref "IC4") (pin "14") (pinfunction "Y5_14") (pintype "tri_state"))
      (node (ref "TFT") (pin "34") (pinfunction "34_34") (pintype "passive"))
    )
    (net (code "84") (name "/SPI_SCK") (class "Default")
      (node (ref "IC4") (pin "4") (pinfunction "A3_4") (pintype "input"))
      (node (ref "U1") (pin "D52") (pinfunction "D52_D52") (pintype "bidirectional"))
    )
    (net (code "85") (name "/SPI_SCK_TFT") (class "Default")
      (node (ref "IC4") (pin "16") (pinfunction "Y3_16") (pintype "tri_state"))
      (node (ref "TFT") (pin "32") (pinfunction "32_32") (pintype "passive"))
    )
    (net (code "86") (name "/SPI_SS") (class "Default")
      (node (ref "IC4") (pin "5") (pinfunction "A4_5") (pintype "input"))
      (node (ref "U1") (pin "D53") (pinfunction "D53_D53") (pintype "bidirectional"))
    )
    (net (code "87") (name "/SPI_SS_TFT") (class "Default")
      (node (ref "IC4") (pin "15") (pinfunction "Y4_15") (pintype "tri_state"))
      (node (ref "TFT") (pin "36") (pinfunction "36_36") (pintype "passive"))
    )
    (net (code "88") (name "/TFT_CS") (class "Default")
      (node (ref "IC4") (pin "17") (pinfunction "Y2_17") (pintype "tri_state"))
      (node (ref "TFT") (pin "29") (pinfunction "29_29") (pintype "passive"))
    )
    (net (code "89") (name "/TFT_LEDA") (class "Default")
      (node (ref "R26") (pin "2") (pinfunction "2_2") (pintype "passive"))
      (node (ref "TFT") (pin "37") (pinfunction "37_37") (pintype "passive"))
    )
    (net (code "90") (name "/TFT_RD") (class "Default")
      (node (ref "R13") (pin "2") (pinfunction "2_2") (pintype "passive"))
      (node (ref "TFT") (pin "11") (pinfunction "11_11") (pintype "passive"))
    )
    (net (code "91") (name "/TFT_REST") (class "Default")
      (node (ref "IC4") (pin "13") (pinfunction "Y6_13") (pintype "tri_state"))
      (node (ref "TFT") (pin "33") (pinfunction "33_33") (pintype "passive"))
    )
    (net (code "92") (name "/TFT_RS") (class "Default")
      (node (ref "IC4") (pin "18") (pinfunction "Y1_18") (pintype "tri_state"))
      (node (ref "TFT") (pin "7") (pinfunction "7_7") (pintype "passive"))
    )
    (net (code "93") (name "/TFT_WR") (class "Default")
      (node (ref "IC4") (pin "12") (pinfunction "Y7_12") (pintype "tri_state"))
      (node (ref "TFT") (pin "9") (pinfunction "9_9") (pintype "passive"))
    )
    (net (code "94") (name "/VIN") (class "Default")
      (node (ref "U1") (pin "VIN") (pinfunction "VIN_VIN") (pintype "bidirectional"))
    )
    (net (code "95") (name "/X-MAX") (class "Default")
      (node (ref "U1") (pin "D17") (pinfunction "D17_D17") (pintype "bidirectional"))
      (node (ref "X-MAX") (pin "3") (pinfunction "3_3") (pintype "passive"))
    )
    (net (code "96") (name "/X-MIN") (class "Default")
      (node (ref "U1") (pin "D16") (pinfunction "D16_D16") (pintype "bidirectional"))
      (node (ref "X-MIN") (pin "3") (pinfunction "3_3") (pintype "passive"))
    )
    (net (code "97") (name "/Y-MAX") (class "Default")
      (node (ref "U1") (pin "D15") (pinfunction "D15_D15") (pintype "bidirectional"))
      (node (ref "Y-MAX") (pin "3") (pinfunction "3_3") (pintype "passive"))
    )
    (net (code "98") (name "/Y-MIN") (class "Default")
      (node (ref "U1") (pin "D14") (pinfunction "D14_D14") (pintype "bidirectional"))
      (node (ref "Y-MIN") (pin "3") (pinfunction "3_3") (pintype "passive"))
    )
    (net (code "99") (name "GND") (class "Default")
      (node (ref "A_STP") (pin "C") (pinfunction "C_C") (pintype "passive"))
      (node (ref "B_STP") (pin "C") (pinfunction "C_C") (pintype "passive"))
      (node (ref "C1") (pin "-") (pinfunction "-_-") (pintype "passive"))
      (node (ref "C10") (pin "1") (pinfunction "1_1") (pintype "passive"))
      (node (ref "C11") (pin "-") (pinfunction "-_-") (pintype "passive"))
      (node (ref "C12") (pin "-") (pinfunction "-_-") (pintype "passive"))
      (node (ref "C13") (pin "1") (pinfunction "1_1") (pintype "passive"))
      (node (ref "C14") (pin "1") (pinfunction "1_1") (pintype "passive"))
      (node (ref "C3") (pin "-") (pinfunction "-_-") (pintype "passive"))
      (node (ref "C4") (pin "-") (pinfunction "-_-") (pintype "passive"))
      (node (ref "C6") (pin "1") (pinfunction "1_1") (pintype "passive"))
      (node (ref "C7") (pin "2") (pinfunction "2_2") (pintype "passive"))
      (node (ref "C9") (pin "2") (pinfunction "2_2") (pintype "passive"))
      (node (ref "C_STP") (pin "C") (pinfunction "C_C") (pintype "passive"))
      (node (ref "D13") (pin "C") (pinfunction "C_C") (pintype "passive"))
      (node (ref "IC1") (pin "GND") (pinfunction "GND_GND") (pintype "bidirectional"))
      (node (ref "IC1") (pin "GND1") (pinfunction "GND1_GND1") (pintype "bidirectional"))
      (node (ref "IC2") (pin "1") (pinfunction "G1_1") (pintype "input"))
      (node (ref "IC2") (pin "10") (pinfunction "GND_10") (pintype "power_in"))
      (node (ref "IC2") (pin "19") (pinfunction "G2_19") (pintype "input"))
      (node (ref "IC3") (pin "1") (pinfunction "G1_1") (pintype "input"))
      (node (ref "IC3") (pin "10") (pinfunction "GND_10") (pintype "power_in"))
      (node (ref "IC3") (pin "19") (pinfunction "G2_19") (pintype "input"))
      (node (ref "IC3") (pin "4") (pinfunction "A3_4") (pintype "input"))
      (node (ref "IC3") (pin "5") (pinfunction "A4_5") (pintype "input"))
      (node (ref "IC3") (pin "6") (pinfunction "A5_6") (pintype "input"))
      (node (ref "IC3") (pin "7") (pinfunction "A6_7") (pintype "input"))
      (node (ref "IC3") (pin "9") (pinfunction "A8_9") (pintype "input"))
      (node (ref "IC4") (pin "1") (pinfunction "G1_1") (pintype "input"))
      (node (ref "IC4") (pin "10") (pinfunction "GND_10") (pintype "power_in"))
      (node (ref "IC4") (pin "19") (pinfunction "G2_19") (pintype "input"))
      (node (ref "IC4") (pin "9") (pinfunction "A8_9") (pintype "input"))
      (node (ref "IC5") (pin "1") (pinfunction "G1_1") (pintype "input"))
      (node (ref "IC5") (pin "10") (pinfunction "GND_10") (pintype "power_in"))
      (node (ref "IC5") (pin "19") (pinfunction "G2_19") (pintype "input"))
      (node (ref "IC5") (pin "2") (pinfunction "A1_2") (pintype "input"))
      (node (ref "IC5") (pin "6") (pinfunction "A5_6") (pintype "input"))
      (node (ref "IC5") (pin "7") (pinfunction "A6_7") (pintype "input"))
      (node (ref "IC5") (pin "8") (pinfunction "A7_8") (pintype "input"))
      (node (ref "IC5") (pin "9") (pinfunction "A8_9") (pintype "input"))
      (node (ref "J1") (pin "2") (pinfunction "2_2") (pintype "passive"))
      (node (ref "PWR") (pin "C") (pinfunction "C_C") (pintype "passive"))
      (node (ref "PWR1") (pin "C") (pinfunction "C_C") (pintype "passive"))
      (node (ref "R1") (pin "2") (pinfunction "2_2") (pintype "passive"))
      (node (ref "R10") (pin "1") (pinfunction "1_1") (pintype "passive"))
      (node (ref "R5") (pin "2") (pinfunction "2_2") (pintype "passive"))
      (node (ref "R7") (pin "1") (pinfunction "1_1") (pintype "passive"))
      (node (ref "R8") (pin "2") (pinfunction "2_2") (pintype "passive"))
      (node (ref "S2") (pin "1") (pinfunction "1_1") (pintype "passive"))
      (node (ref "S2") (pin "2") (pinfunction "2_2") (pintype "passive"))
      (node (ref "SER1") (pin "1") (pinfunction "1_1") (pintype "passive"))
      (node (ref "SER2") (pin "1") (pinfunction "1_1") (pintype "passive"))
      (node (ref "TFT") (pin "1") (pinfunction "1_1") (pintype "passive"))
      (node (ref "TFT") (pin "10") (pinfunction "10_10") (pintype "passive"))
      (node (ref "TFT") (pin "12") (pinfunction "12_12") (pintype "passive"))
      (node (ref "TFT") (pin "14") (pinfunction "14_14") (pintype "passive"))
      (node (ref "TFT") (pin "16") (pinfunction "16_16") (pintype "passive"))
      (node (ref "TFT") (pin "2") (pinfunction "2_2") (pintype "passive"))
      (node (ref "TFT") (pin "4") (pinfunction "4_4") (pintype "passive"))
      (node (ref "TFT") (pin "6") (pinfunction "6_6") (pintype "passive"))
      (node (ref "TFT") (pin "8") (pinfunction "8_8") (pintype "passive"))
      (node (ref "U$1") (pin "GND") (pinfunction "GND_GND") (pintype "power_in"))
      (node (ref "U$1") (pin "GND@0") (pinfunction "GND_GND@0") (pintype "power_in"))
      (node (ref "U$6") (pin "GND") (pinfunction "GND_GND") (pintype "power_in"))
      (node (ref "U$6") (pin "GND@0") (pinfunction "GND_GND@0") (pintype "power_in"))
      (node (ref "U$7") (pin "GND") (pinfunction "GND_GND") (pintype "power_in"))
      (node (ref "U$7") (pin "GND@0") (pinfunction "GND_GND@0") (pintype "power_in"))
      (node (ref "U1") (pin "GND@0") (pinfunction "GND_GND@0") (pintype "power_in"))
      (node (ref "U1") (pin "GND@1") (pinfunction "GND_GND@1") (pintype "power_in"))
      (node (ref "U1") (pin "GND@2") (pinfunction "GND_GND@2") (pintype "power_in"))
      (node (ref "U1") (pin "GND@3") (pinfunction "GND_GND@3") (pintype "power_in"))
      (node (ref "U1") (pin "GND@4") (pinfunction "GND_GND@4") (pintype "power_in"))
      (node (ref "X-MAX") (pin "1") (pinfunction "1_1") (pintype "passive"))
      (node (ref "X-MIN") (pin "1") (pinfunction "1_1") (pintype "passive"))
      (node (ref "X1") (pin "RING") (pinfunction "RING_RING") (pintype "bidirectional"))
      (node (ref "X1") (pin "RING_SW") (pinfunction "RING_SW_RING_SW") (pintype "bidirectional"))
      (node (ref "Y-MAX") (pin "1") (pinfunction "1_1") (pintype "passive"))
      (node (ref "Y-MIN") (pin "1") (pinfunction "1_1") (pintype "passive"))
    )
    (net (code "100") (name "Net-(A-MOT1-Pad1)") (class "Default")
      (node (ref "A-MOT1") (pin "1") (pinfunction "1_1") (pintype "bidirectional"))
      (node (ref "A-MOT2") (pin "1") (pinfunction "1_1") (pintype "passive"))
      (node (ref "U$1") (pin "2B") (pinfunction "2B_2B") (pintype "output"))
    )
    (net (code "101") (name "Net-(A-MOT1-Pad2)") (class "Default")
      (node (ref "A-MOT1") (pin "2") (pinfunction "2_2") (pintype "bidirectional"))
      (node (ref "A-MOT2") (pin "2") (pinfunction "2_2") (pintype "passive"))
      (node (ref "U$1") (pin "2A") (pinfunction "2A_2A") (pintype "output"))
    )
    (net (code "102") (name "Net-(A-MOT1-Pad3)") (class "Default")
      (node (ref "A-MOT1") (pin "3") (pinfunction "3_3") (pintype "bidirectional"))
      (node (ref "A-MOT2") (pin "3") (pinfunction "3_3") (pintype "passive"))
      (node (ref "U$1") (pin "1A") (pinfunction "1A_1A") (pintype "output"))
    )
    (net (code "103") (name "Net-(A-MOT1-Pad4)") (class "Default")
      (node (ref "A-MOT1") (pin "4") (pinfunction "4_4") (pintype "bidirectional"))
      (node (ref "A-MOT2") (pin "4") (pinfunction "4_4") (pintype "passive"))
      (node (ref "U$1") (pin "1B") (pinfunction "1B_1B") (pintype "output"))
    )
    (net (code "104") (name "Net-(A_STP-PadA)") (class "Default")
      (node (ref "A_STP") (pin "A") (pinfunction "A_A") (pintype "passive"))
      (node (ref "R6") (pin "1") (pinfunction "1_1") (pintype "passive"))
    )
    (net (code "105") (name "Net-(B-MOT1-Pad1)") (class "Default")
      (node (ref "B-MOT1") (pin "1") (pinfunction "1_1") (pintype "bidirectional"))
      (node (ref "B-MOT2") (pin "1") (pinfunction "1_1") (pintype "passive"))
      (node (ref "U$7") (pin "2B") (pinfunction "2B_2B") (pintype "output"))
    )
    (net (code "106") (name "Net-(B-MOT1-Pad2)") (class "Default")
      (node (ref "B-MOT1") (pin "2") (pinfunction "2_2") (pintype "bidirectional"))
      (node (ref "B-MOT2") (pin "2") (pinfunction "2_2") (pintype "passive"))
      (node (ref "U$7") (pin "2A") (pinfunction "2A_2A") (pintype "output"))
    )
    (net (code "107") (name "Net-(B-MOT1-Pad3)") (class "Default")
      (node (ref "B-MOT1") (pin "3") (pinfunction "3_3") (pintype "bidirectional"))
      (node (ref "B-MOT2") (pin "3") (pinfunction "3_3") (pintype "passive"))
      (node (ref "U$7") (pin "1A") (pinfunction "1A_1A") (pintype "output"))
    )
    (net (code "108") (name "Net-(B-MOT1-Pad4)") (class "Default")
      (node (ref "B-MOT1") (pin "4") (pinfunction "4_4") (pintype "bidirectional"))
      (node (ref "B-MOT2") (pin "4") (pinfunction "4_4") (pintype "passive"))
      (node (ref "U$7") (pin "1B") (pinfunction "1B_1B") (pintype "output"))
    )
    (net (code "109") (name "Net-(B_STP-PadA)") (class "Default")
      (node (ref "B_STP") (pin "A") (pinfunction "A_A") (pintype "passive"))
      (node (ref "R11") (pin "1") (pinfunction "1_1") (pintype "passive"))
    )
    (net (code "110") (name "Net-(C-MOT1-Pad1)") (class "Default")
      (node (ref "C-MOT1") (pin "1") (pinfunction "1_1") (pintype "bidirectional"))
      (node (ref "C-MOT2") (pin "1") (pinfunction "1_1") (pintype "passive"))
      (node (ref "U$6") (pin "2B") (pinfunction "2B_2B") (pintype "output"))
    )
    (net (code "111") (name "Net-(C-MOT1-Pad2)") (class "Default")
      (node (ref "C-MOT1") (pin "2") (pinfunction "2_2") (pintype "bidirectional"))
      (node (ref "C-MOT2") (pin "2") (pinfunction "2_2") (pintype "passive"))
      (node (ref "U$6") (pin "2A") (pinfunction "2A_2A") (pintype "output"))
    )
    (net (code "112") (name "Net-(C-MOT1-Pad3)") (class "Default")
      (node (ref "C-MOT1") (pin "3") (pinfunction "3_3") (pintype "bidirectional"))
      (node (ref "C-MOT2") (pin "3") (pinfunction "3_3") (pintype "passive"))
      (node (ref "U$6") (pin "1A") (pinfunction "1A_1A") (pintype "output"))
    )
    (net (code "113") (name "Net-(C-MOT1-Pad4)") (class "Default")
      (node (ref "C-MOT1") (pin "4") (pinfunction "4_4") (pintype "bidirectional"))
      (node (ref "C-MOT2") (pin "4") (pinfunction "4_4") (pintype "passive"))
      (node (ref "U$6") (pin "1B") (pinfunction "1B_1B") (pintype "output"))
    )
    (net (code "114") (name "Net-(C5-Pad1)") (class "Default")
      (node (ref "C5") (pin "1") (pinfunction "1_1") (pintype "passive"))
      (node (ref "IC1") (pin "COMP") (pinfunction "COMP_COMP") (pintype "bidirectional"))
    )
    (net (code "115") (name "Net-(C5-Pad2)") (class "Default")
      (node (ref "C5") (pin "2") (pinfunction "2_2") (pintype "passive"))
      (node (ref "R7") (pin "2") (pinfunction "2_2") (pintype "passive"))
    )
    (net (code "116") (name "Net-(C8-Pad1)") (class "Default")
      (node (ref "C8") (pin "1") (pinfunction "1_1") (pintype "passive"))
      (node (ref "IC1") (pin "BS") (pinfunction "BS_BS") (pintype "bidirectional"))
    )
    (net (code "117") (name "Net-(C8-Pad2)") (class "Default")
      (node (ref "C8") (pin "2") (pinfunction "2_2") (pintype "passive"))
      (node (ref "IC1") (pin "SW") (pinfunction "SW_SW") (pintype "bidirectional"))
      (node (ref "L1") (pin "1") (pinfunction "1_1") (pintype "passive"))
    )
    (net (code "118") (name "Net-(C9-Pad1)") (class "Default")
      (node (ref "C9") (pin "1") (pinfunction "1_1") (pintype "passive"))
      (node (ref "IC1") (pin "SS") (pinfunction "SS_SS") (pintype "bidirectional"))
    )
    (net (code "119") (name "Net-(C12-Pad+)") (class "Default")
      (node (ref "C12") (pin "+") (pinfunction "+_+") (pintype "passive"))
      (node (ref "C7") (pin "1") (pinfunction "1_1") (pintype "passive"))
      (node (ref "L1") (pin "2") (pinfunction "2_2") (pintype "passive"))
      (node (ref "ON_BOARD_PWR") (pin "2") (pinfunction "2_2") (pintype "passive"))
      (node (ref "R12") (pin "1") (pinfunction "1_1") (pintype "passive"))
      (node (ref "R9") (pin "2") (pinfunction "2_2") (pintype "passive"))
    )
    (net (code "120") (name "Net-(C_STP-PadA)") (class "Default")
      (node (ref "C_STP") (pin "A") (pinfunction "A_A") (pintype "passive"))
      (node (ref "R3") (pin "1") (pinfunction "1_1") (pintype "passive"))
    )
    (net (code "121") (name "Net-(D2-PadA)") (class "Default")
      (node (ref "D2") (pin "A") (pinfunction "A_A") (pintype "passive"))
      (node (ref "ON_BOARD_PWR") (pin "1") (pinfunction "1_1") (pintype "passive"))
    )
    (net (code "122") (name "Net-(D13-PadA)") (class "Default")
      (node (ref "D13") (pin "A") (pinfunction "A_A") (pintype "passive"))
      (node (ref "RN1") (pin "1") (pinfunction "1_1") (pintype "passive"))
    )
    (net (code "123") (name "Net-(IC1-PadEN)") (class "Default")
      (node (ref "IC1") (pin "EN") (pinfunction "EN_EN") (pintype "bidirectional"))
      (node (ref "R4") (pin "2") (pinfunction "2_2") (pintype "passive"))
    )
    (net (code "124") (name "Net-(IC1-PadFB)") (class "Default")
      (node (ref "IC1") (pin "FB") (pinfunction "FB_FB") (pintype "bidirectional"))
      (node (ref "R10") (pin "2") (pinfunction "2_2") (pintype "passive"))
      (node (ref "R9") (pin "1") (pinfunction "1_1") (pintype "passive"))
    )
    (net (code "125") (name "Net-(PWR1-PadA)") (class "Default")
      (node (ref "PWR1") (pin "A") (pinfunction "A_A") (pintype "passive"))
      (node (ref "R12") (pin "2") (pinfunction "2_2") (pintype "passive"))
    )
    (net (code "126") (name "Net-(R1-Pad1)") (class "Default")
      (node (ref "R1") (pin "1") (pinfunction "1_1") (pintype "passive"))
      (node (ref "SJ7") (pin "2") (pinfunction "2_2") (pintype "passive"))
      (node (ref "U$1") (pin "MS1") (pinfunction "MS1_MS1") (pintype "input"))
    )
    (net (code "127") (name "Net-(R5-Pad1)") (class "Default")
      (node (ref "R5") (pin "1") (pinfunction "1_1") (pintype "passive"))
      (node (ref "SJ1") (pin "2") (pinfunction "2_2") (pintype "passive"))
      (node (ref "U$6") (pin "MS1") (pinfunction "MS1_MS1") (pintype "input"))
    )
    (net (code "128") (name "Net-(R8-Pad1)") (class "Default")
      (node (ref "R8") (pin "1") (pinfunction "1_1") (pintype "passive"))
      (node (ref "SJ3") (pin "2") (pinfunction "2_2") (pintype "passive"))
      (node (ref "U$7") (pin "MS1") (pinfunction "MS1_MS1") (pintype "input"))
    )
    (net (code "129") (name "Net-(RN1B-1)") (class "Default")
      (node (ref "RN1") (pin "2") (pinfunction "1_2") (pintype "passive"))
      (node (ref "RX_LED") (pin "C") (pinfunction "C_C") (pintype "passive"))
    )
    (net (code "130") (name "Net-(RN1C-1)") (class "Default")
      (node (ref "RN1") (pin "3") (pinfunction "1_3") (pintype "passive"))
      (node (ref "TX_LED") (pin "C") (pinfunction "C_C") (pintype "passive"))
    )
    (net (code "131") (name "Net-(RN1D-1)") (class "Default")
      (node (ref "PWR") (pin "A") (pinfunction "A_A") (pintype "passive"))
      (node (ref "RN1") (pin "4") (pinfunction "1_4") (pintype "passive"))
    )
    (net (code "132") (name "Net-(SJ2-Pad2)") (class "Default")
      (node (ref "SJ2") (pin "2") (pinfunction "2_2") (pintype "passive"))
      (node (ref "U$6") (pin "MS2") (pinfunction "MS2_MS2") (pintype "input"))
    )
    (net (code "133") (name "Net-(SJ4-Pad2)") (class "Default")
      (node (ref "SJ4") (pin "2") (pinfunction "2_2") (pintype "passive"))
      (node (ref "U$7") (pin "MS2") (pinfunction "MS2_MS2") (pintype "input"))
    )
    (net (code "134") (name "Net-(SJ5-Pad2)") (class "Default")
      (node (ref "SJ5") (pin "2") (pinfunction "2_2") (pintype "passive"))
      (node (ref "U$6") (pin "MS3") (pinfunction "MS3_MS3") (pintype "input"))
    )
    (net (code "135") (name "Net-(SJ6-Pad2)") (class "Default")
      (node (ref "SJ6") (pin "2") (pinfunction "2_2") (pintype "passive"))
      (node (ref "U$7") (pin "MS3") (pinfunction "MS3_MS3") (pintype "input"))
    )
    (net (code "136") (name "Net-(SJ8-Pad2)") (class "Default")
      (node (ref "SJ8") (pin "2") (pinfunction "2_2") (pintype "passive"))
      (node (ref "U$1") (pin "MS2") (pinfunction "MS2_MS2") (pintype "input"))
    )
    (net (code "137") (name "Net-(SJ9-Pad2)") (class "Default")
      (node (ref "SJ9") (pin "2") (pinfunction "2_2") (pintype "passive"))
      (node (ref "U$1") (pin "MS3") (pinfunction "MS3_MS3") (pintype "input"))
    )
    (net (code "138") (name "Net-(U$1-SLEEP)") (class "Default")
      (node (ref "U$1") (pin "RST") (pinfunction "RST_RST") (pintype "input"))
      (node (ref "U$1") (pin "SLP") (pinfunction "SLEEP_SLP") (pintype "input"))
    )
    (net (code "139") (name "Net-(U$6-SLEEP)") (class "Default")
      (node (ref "U$6") (pin "RST") (pinfunction "RST_RST") (pintype "input"))
      (node (ref "U$6") (pin "SLP") (pinfunction "SLEEP_SLP") (pintype "input"))
    )
    (net (code "140") (name "Net-(U$7-SLEEP)") (class "Default")
      (node (ref "U$7") (pin "RST") (pinfunction "RST_RST") (pintype "input"))
      (node (ref "U$7") (pin "SLP") (pinfunction "SLEEP_SLP") (pintype "input"))
    )
    (net (code "141") (name "VCC") (class "Default")
      (node (ref "D2") (pin "C") (pinfunction "C_C") (pintype "passive"))
      (node (ref "IC5") (pin "20") (pinfunction "VCC_20") (pintype "power_in"))
      (node (ref "R18") (pin "1") (pinfunction "1_1") (pintype "passive"))
      (node (ref "R19") (pin "1") (pinfunction "1_1") (pintype "passive"))
      (node (ref "R2") (pin "1") (pinfunction "1_1") (pintype "passive"))
      (node (ref "RN1") (pin "5") (pinfunction "2_5") (pintype "passive"))
      (node (ref "RX_LED") (pin "A") (pinfunction "A_A") (pintype "passive"))
      (node (ref "SER1") (pin "2") (pinfunction "2_2") (pintype "passive"))
      (node (ref "SER2") (pin "2") (pinfunction "2_2") (pintype "passive"))
      (node (ref "SJ1") (pin "1") (pinfunction "1_1") (pintype "passive"))
      (node (ref "SJ2") (pin "1") (pinfunction "1_1") (pintype "passive"))
      (node (ref "SJ3") (pin "1") (pinfunction "1_1") (pintype "passive"))
      (node (ref "SJ4") (pin "1") (pinfunction "1_1") (pintype "passive"))
      (node (ref "SJ5") (pin "1") (pinfunction "1_1") (pintype "passive"))
      (node (ref "SJ6") (pin "1") (pinfunction "1_1") (pintype "passive"))
      (node (ref "SJ7") (pin "1") (pinfunction "1_1") (pintype "passive"))
      (node (ref "SJ8") (pin "1") (pinfunction "1_1") (pintype "passive"))
      (node (ref "SJ9") (pin "1") (pinfunction "1_1") (pintype "passive"))
      (node (ref "TFT") (pin "3") (pinfunction "3_3") (pintype "passive"))
      (node (ref "TX_LED") (pin "A") (pinfunction "A_A") (pintype "passive"))
      (node (ref "U$1") (pin "VDD") (pinfunction "VDD_VDD") (pintype "power_in"))
      (node (ref "U$6") (pin "VDD") (pinfunction "VDD_VDD") (pintype "power_in"))
      (node (ref "U$7") (pin "VDD") (pinfunction "VDD_VDD") (pintype "power_in"))
      (node (ref "U1") (pin "5V@0") (pinfunction "5V_5V@0") (pintype "power_in"))
      (node (ref "U1") (pin "5V@1") (pinfunction "5V_5V@1") (pintype "power_in"))
      (node (ref "U1") (pin "5V@2") (pinfunction "5V_5V@2") (pintype "power_in"))
      (node (ref "X-MAX") (pin "2") (pinfunction "2_2") (pintype "passive"))
      (node (ref "X-MIN") (pin "2") (pinfunction "2_2") (pintype "passive"))
      (node (ref "Y-MAX") (pin "2") (pinfunction "2_2") (pintype "passive"))
      (node (ref "Y-MIN") (pin "2") (pinfunction "2_2") (pintype "passive"))
    )
    (net (code "142") (name "unconnected-(D1-PadA)") (class "Default")
      (node (ref "D1") (pin "A") (pinfunction "A_A") (pintype "passive"))
    )
    (net (code "143") (name "unconnected-(D1-PadC)") (class "Default")
      (node (ref "D1") (pin "C") (pinfunction "C_C") (pintype "passive"))
    )
    (net (code "144") (name "unconnected-(IC3A-Y3-Pad16)") (class "Default")
      (node (ref "IC3") (pin "16") (pinfunction "Y3_16") (pintype "tri_state"))
    )
    (net (code "145") (name "unconnected-(IC3A-Y4-Pad15)") (class "Default")
      (node (ref "IC3") (pin "15") (pinfunction "Y4_15") (pintype "tri_state"))
    )
    (net (code "146") (name "unconnected-(IC3A-Y5-Pad14)") (class "Default")
      (node (ref "IC3") (pin "14") (pinfunction "Y5_14") (pintype "tri_state"))
    )
    (net (code "147") (name "unconnected-(IC3A-Y6-Pad13)") (class "Default")
      (node (ref "IC3") (pin "13") (pinfunction "Y6_13") (pintype "tri_state"))
    )
    (net (code "148") (name "unconnected-(IC3A-Y8-Pad11)") (class "Default")
      (node (ref "IC3") (pin "11") (pinfunction "Y8_11") (pintype "tri_state"))
    )
    (net (code "149") (name "unconnected-(IC4A-Y8-Pad11)") (class "Default")
      (node (ref "IC4") (pin "11") (pinfunction "Y8_11") (pintype "tri_state"))
    )
    (net (code "150") (name "unconnected-(IC5A-Y1-Pad18)") (class "Default")
      (node (ref "IC5") (pin "18") (pinfunction "Y1_18") (pintype "tri_state"))
    )
    (net (code "151") (name "unconnected-(IC5A-Y5-Pad14)") (class "Default")
      (node (ref "IC5") (pin "14") (pinfunction "Y5_14") (pintype "tri_state"))
    )
    (net (code "152") (name "unconnected-(IC5A-Y6-Pad13)") (class "Default")
      (node (ref "IC5") (pin "13") (pinfunction "Y6_13") (pintype "tri_state"))
    )
    (net (code "153") (name "unconnected-(IC5A-Y7-Pad12)") (class "Default")
      (node (ref "IC5") (pin "12") (pinfunction "Y7_12") (pintype "tri_state"))
    )
    (net (code "154") (name "unconnected-(IC5A-Y8-Pad11)") (class "Default")
      (node (ref "IC5") (pin "11") (pinfunction "Y8_11") (pintype "tri_state"))
    )
    (net (code "155") (name "unconnected-(TFT-Pad5)") (class "Default")
      (node (ref "TFT") (pin "5") (pinfunction "5_5") (pintype "passive"))
    )
    (net (code "156") (name "unconnected-(TFT-Pad24)") (class "Default")
      (node (ref "TFT") (pin "24") (pinfunction "24_24") (pintype "passive"))
    )
    (net (code "157") (name "unconnected-(TFT-Pad31)") (class "Default")
      (node (ref "TFT") (pin "31") (pinfunction "31_31") (pintype "passive"))
    )
    (net (code "158") (name "unconnected-(TFT-Pad35)") (class "Default")
      (node (ref "TFT") (pin "35") (pinfunction "35_35") (pintype "passive"))
    )
    (net (code "159") (name "unconnected-(TFT-Pad38)") (class "Default")
      (node (ref "TFT") (pin "38") (pinfunction "38_38") (pintype "passive"))
    )
    (net (code "160") (name "unconnected-(TFT-Pad39)") (class "Default")
      (node (ref "TFT") (pin "39") (pinfunction "39_39") (pintype "passive"))
    )
    (net (code "161") (name "unconnected-(TFT-Pad40)") (class "Default")
      (node (ref "TFT") (pin "40") (pinfunction "40_40") (pintype "passive"))
    )
  )
)
